# MatrixClock.net
KiCad netlist of a schematic drawn in EasyEDA Pro
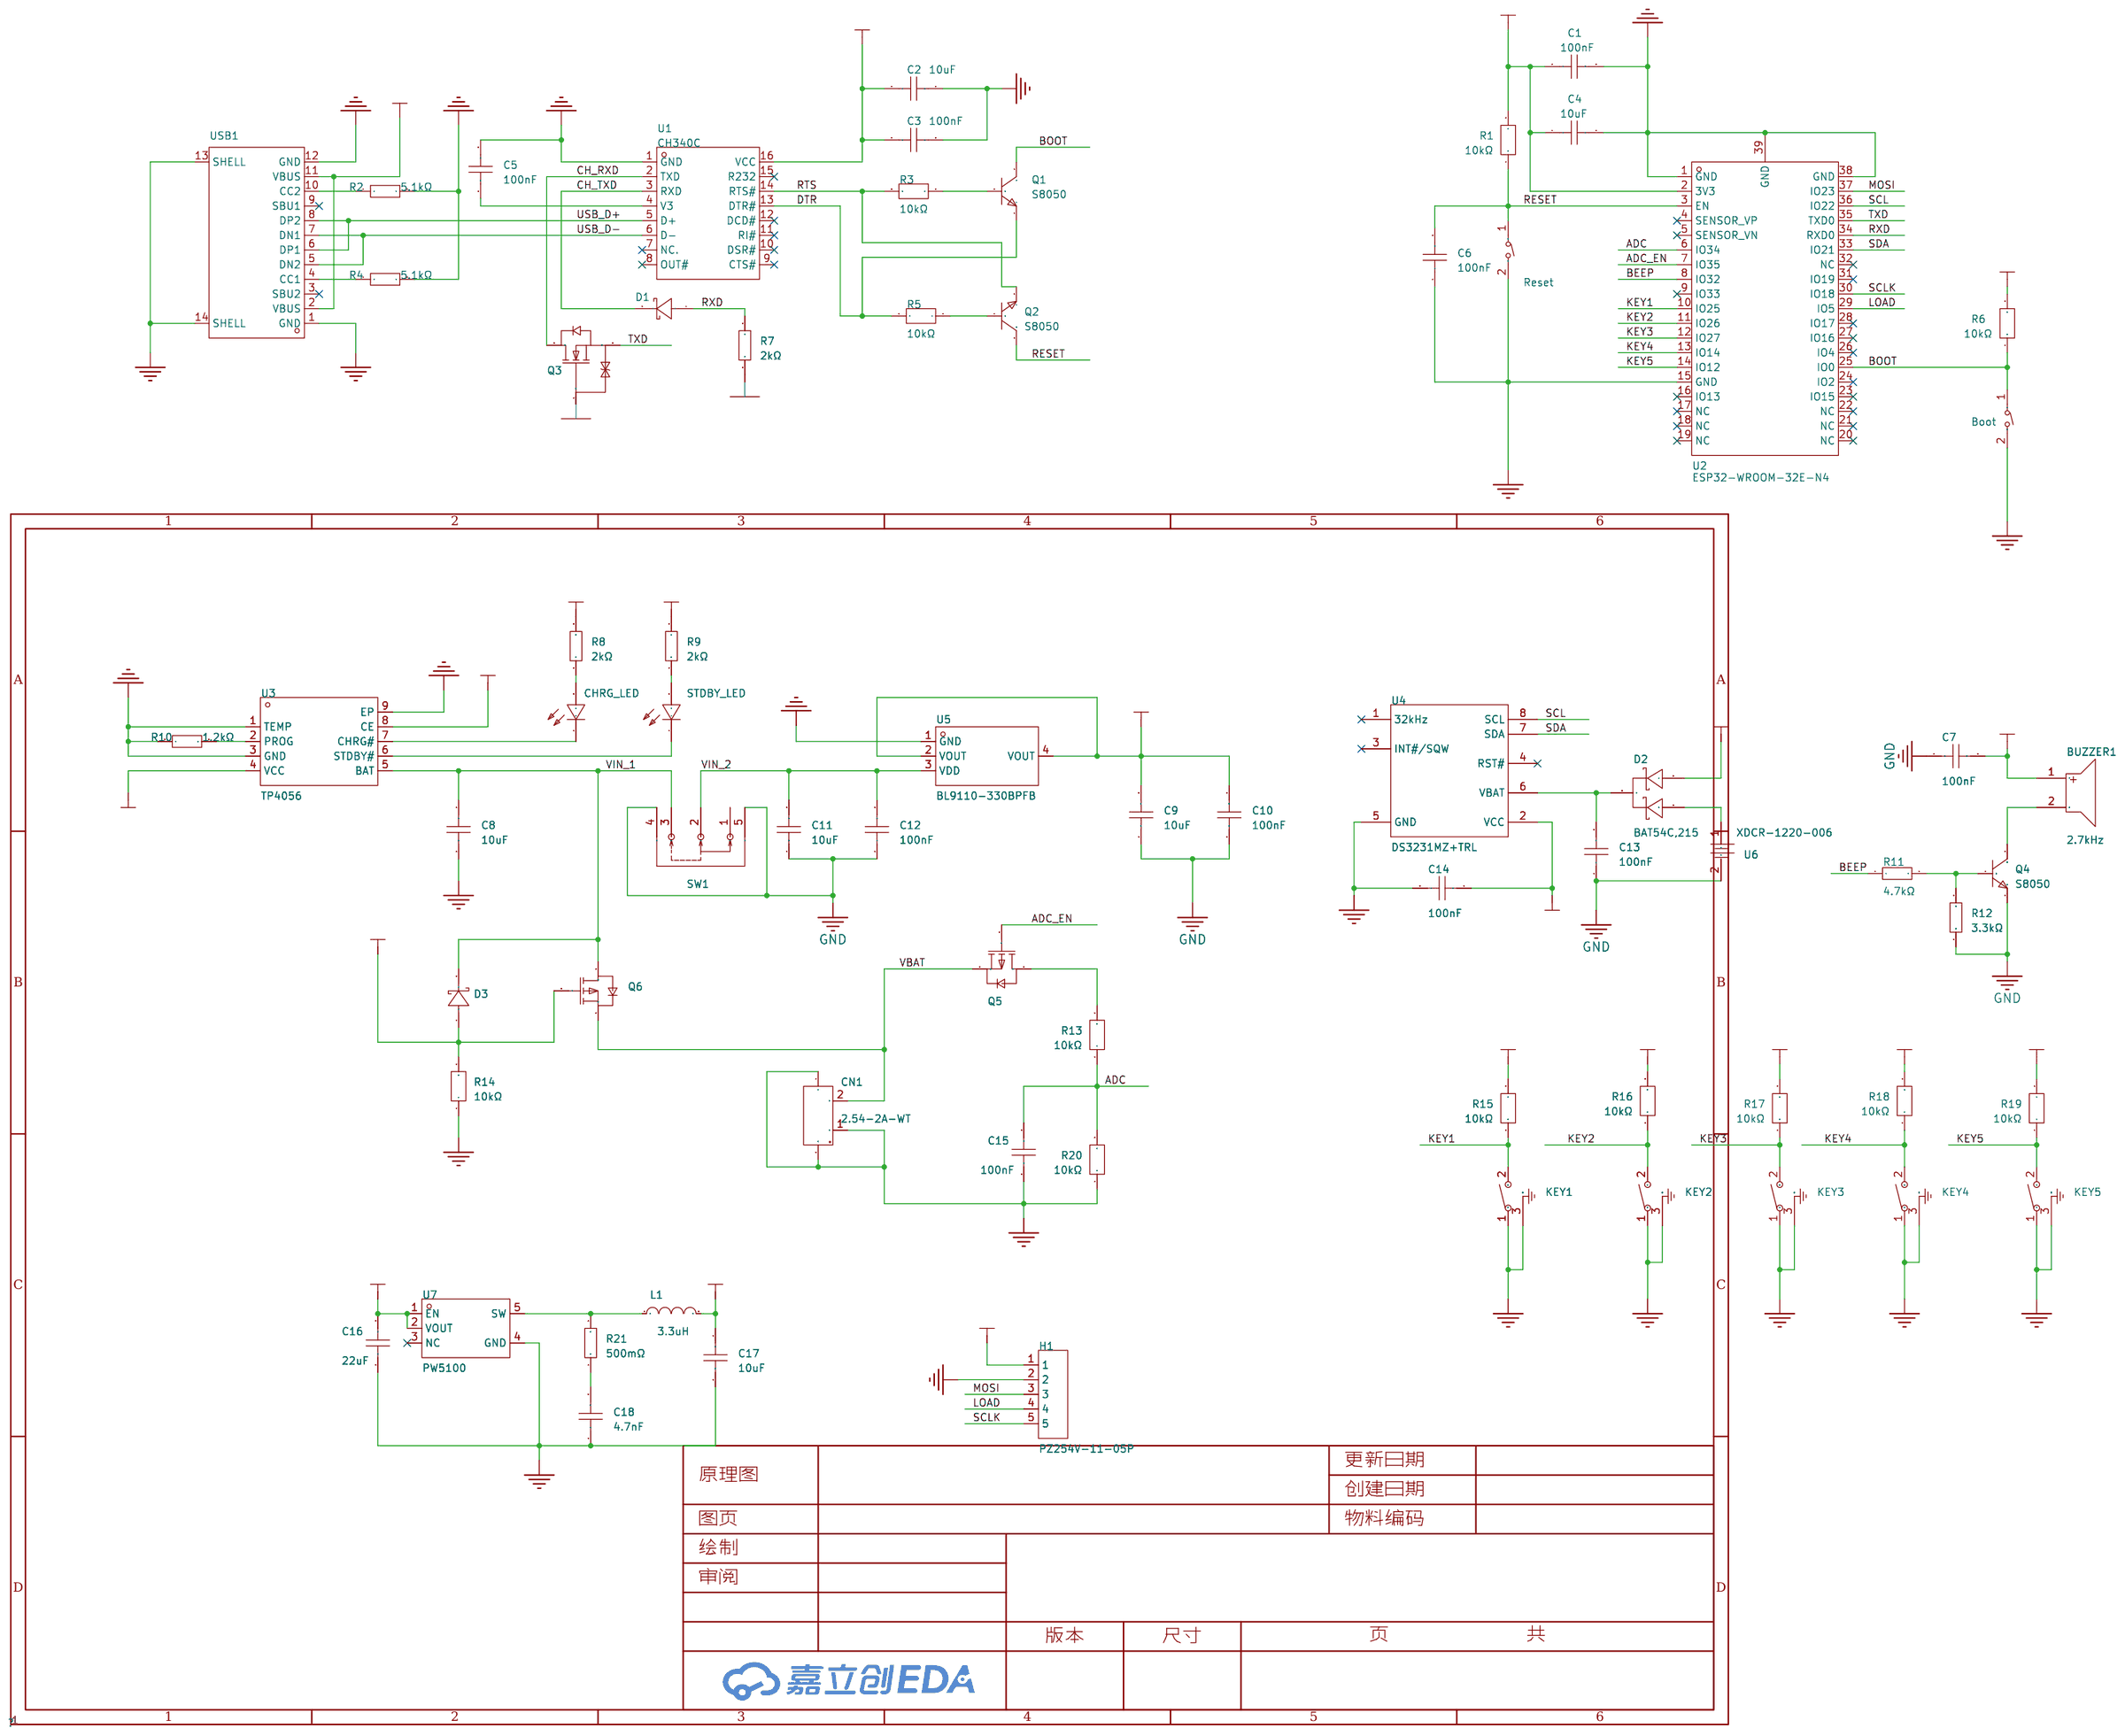
[diagram p0: schematic sheet]

(export (version "E")
  (design (tool "Eeschema 10.0.6"))
  (components
    (comp (ref "Boot")
      (value "ZX-QC34-2TPDZ")
      (fields (field (name "Manufacturer") "Megastar(兆星)"))
      (libsource (lib "easyedapro") (part "ZX-QC36-4.3TPWD"))
    )
    (comp (ref "BUZZER1")
      (value "2.7kHz")
      (footprint "easyedapro:BUZ-TH_BD9.0-P4.00-D0.6-FD")
      (description "驱动方式:无源(外部驱动);构造类型:电磁式;频率:2.7kHz;声压(SPL):85dB;")
      (fields (field (name "Manufacturer Part") "QMB-09B-03") (field (name "Manufacturer") "华能"))
      (libsource (lib "easyedapro") (part "QMB-09B-03"))
    )
    (comp (ref "C1")
      (value "100nF")
      (footprint "easyedapro:C0603")
      (description "容值:100nF;精度:±10%;额定电压:50V;材质(温度系数):X7R;")
      (fields
        (field (name "Manufacturer Part") "CC0603KRX7R9BB104")
        (field (name "Manufacturer") "YAGEO(国巨)")
      )
      (libsource (lib "easyedapro") (part "CC0603KRX7R9BB104"))
    )
    (comp (ref "C2")
      (value "10uF")
      (footprint "easyedapro:C0603")
      (description "容值:10uF;精度:±20%;额定电压:25V;材质(温度系数):X5R;")
      (fields
        (field (name "Manufacturer Part") "CL10A106MA8NRNC")
        (field (name "Manufacturer") "SAMSUNG(三星)")
      )
      (libsource (lib "easyedapro") (part "CL10A106MA8NRNC"))
    )
    (comp (ref "C3")
      (value "100nF")
      (footprint "easyedapro:C0603")
      (description "容值:100nF;精度:±10%;额定电压:50V;材质(温度系数):X7R;")
      (fields
        (field (name "Manufacturer Part") "CC0603KRX7R9BB104")
        (field (name "Manufacturer") "YAGEO(国巨)")
      )
      (libsource (lib "easyedapro") (part "CC0603KRX7R9BB104"))
    )
    (comp (ref "C4")
      (value "10uF")
      (footprint "easyedapro:C0603")
      (description "容值:10uF;精度:±20%;额定电压:25V;材质(温度系数):X5R;")
      (fields
        (field (name "Manufacturer Part") "CL10A106MA8NRNC")
        (field (name "Manufacturer") "SAMSUNG(三星)")
      )
      (libsource (lib "easyedapro") (part "CL10A106MA8NRNC"))
    )
    (comp (ref "C5")
      (value "100nF")
      (footprint "easyedapro:C0603")
      (description "容值:100nF;精度:±10%;额定电压:50V;材质(温度系数):X7R;")
      (fields
        (field (name "Manufacturer Part") "CC0603KRX7R9BB104")
        (field (name "Manufacturer") "YAGEO(国巨)")
      )
      (libsource (lib "easyedapro") (part "CC0603KRX7R9BB104"))
    )
    (comp (ref "C6")
      (value "100nF")
      (footprint "easyedapro:C0603")
      (description "容值:100nF;精度:±10%;额定电压:50V;材质(温度系数):X7R;")
      (fields
        (field (name "Manufacturer Part") "CC0603KRX7R9BB104")
        (field (name "Manufacturer") "YAGEO(国巨)")
      )
      (libsource (lib "easyedapro") (part "CC0603KRX7R9BB104"))
    )
    (comp (ref "C7")
      (value "100nF")
      (footprint "easyedapro:C0603")
      (description "容值:100nF;精度:±10%;额定电压:50V;材质(温度系数):X7R;")
      (fields
        (field (name "Manufacturer Part") "CC0603KRX7R9BB104")
        (field (name "Manufacturer") "YAGEO(国巨)")
      )
      (libsource (lib "easyedapro") (part "CC0603KRX7R9BB104"))
    )
    (comp (ref "C8")
      (value "10uF")
      (footprint "easyedapro:C0603")
      (description "容值:10uF;精度:±20%;额定电压:25V;材质(温度系数):X5R;")
      (fields
        (field (name "Manufacturer Part") "CL10A106MA8NRNC")
        (field (name "Manufacturer") "SAMSUNG(三星)")
      )
      (libsource (lib "easyedapro") (part "CL10A106MA8NRNC"))
    )
    (comp (ref "C9")
      (value "10uF")
      (footprint "easyedapro:C0603")
      (description "容值:10uF;精度:±20%;额定电压:25V;材质(温度系数):X5R;")
      (fields
        (field (name "Manufacturer Part") "CL10A106MA8NRNC")
        (field (name "Manufacturer") "SAMSUNG(三星)")
      )
      (libsource (lib "easyedapro") (part "CL10A106MA8NRNC"))
    )
    (comp (ref "C10")
      (value "100nF")
      (footprint "easyedapro:C0603")
      (description "容值:100nF;精度:±10%;额定电压:50V;材质(温度系数):X7R;")
      (fields
        (field (name "Manufacturer Part") "CC0603KRX7R9BB104")
        (field (name "Manufacturer") "YAGEO(国巨)")
      )
      (libsource (lib "easyedapro") (part "CC0603KRX7R9BB104"))
    )
    (comp (ref "C11")
      (value "10uF")
      (footprint "easyedapro:C0603")
      (description "容值:10uF;精度:±20%;额定电压:25V;材质(温度系数):X5R;")
      (fields
        (field (name "Manufacturer Part") "CL10A106MA8NRNC")
        (field (name "Manufacturer") "SAMSUNG(三星)")
      )
      (libsource (lib "easyedapro") (part "CL10A106MA8NRNC"))
    )
    (comp (ref "C12")
      (value "100nF")
      (footprint "easyedapro:C0603")
      (description "容值:100nF;精度:±10%;额定电压:50V;材质(温度系数):X7R;")
      (fields
        (field (name "Manufacturer Part") "CC0603KRX7R9BB104")
        (field (name "Manufacturer") "YAGEO(国巨)")
      )
      (libsource (lib "easyedapro") (part "CC0603KRX7R9BB104"))
    )
    (comp (ref "C13")
      (value "100nF")
      (footprint "easyedapro:C0603")
      (description "容值:100nF;精度:±10%;额定电压:50V;材质(温度系数):X7R;")
      (fields
        (field (name "Manufacturer Part") "CC0603KRX7R9BB104")
        (field (name "Manufacturer") "YAGEO(国巨)")
      )
      (libsource (lib "easyedapro") (part "CC0603KRX7R9BB104"))
    )
    (comp (ref "C14")
      (value "100nF")
      (footprint "easyedapro:C0603")
      (description "容值:100nF;精度:±10%;额定电压:50V;材质(温度系数):X7R;")
      (fields
        (field (name "Manufacturer Part") "CC0603KRX7R9BB104")
        (field (name "Manufacturer") "YAGEO(国巨)")
      )
      (libsource (lib "easyedapro") (part "CC0603KRX7R9BB104"))
    )
    (comp (ref "C15")
      (value "100nF")
      (footprint "easyedapro:C0603")
      (description "容值:100nF;精度:±10%;额定电压:50V;材质(温度系数):X7R;")
      (fields
        (field (name "Manufacturer Part") "CC0603KRX7R9BB104")
        (field (name "Manufacturer") "YAGEO(国巨)")
      )
      (libsource (lib "easyedapro") (part "CC0603KRX7R9BB104"))
    )
    (comp (ref "C16")
      (value "22uF")
      (fields
        (field (name "Manufacturer Part") "CGA0603X5R226M160JT")
        (field (name "Manufacturer") "HRE(芯声)")
      )
      (libsource (lib "easyedapro") (part "CapAcitance"))
    )
    (comp (ref "C17")
      (value "10uF")
      (footprint "easyedapro:C0603")
      (description "容值:10uF;精度:±20%;额定电压:25V;材质(温度系数):X5R;")
      (fields
        (field (name "Manufacturer Part") "CL10A106MA8NRNC")
        (field (name "Manufacturer") "SAMSUNG(三星)")
      )
      (libsource (lib "easyedapro") (part "CL10A106MA8NRNC"))
    )
    (comp (ref "C18")
      (value "4.7nF")
      (footprint "easyedapro:C0603")
      (description "容值:4.7nF;精度:±10%;额定电压:50V;材质(温度系数):X7R;")
      (fields
        (field (name "Manufacturer Part") "CGA0603X7R472K500JT")
        (field (name "Manufacturer") "HRE(芯声)")
      )
      (libsource (lib "easyedapro") (part "CGA0603X7R472K500JT"))
    )
    (comp (ref "CHRG_LED")
      (value "NCD0603R1")
      (footprint "easyedapro:LED0603-RD_RED")
      (fields (field (name "Manufacturer") "国星光电"))
      (libsource (lib "easyedapro") (part "FC-DA1608HRK-620D"))
    )
    (comp (ref "CN1")
      (value "2.54-2A-WT")
      (footprint "easyedapro:CONN-SMD_2.54-2A-WT")
      (description "插针结构:1x2P;间距:2.54mm;安装方式:卧贴;参考系列:XH;总PIN数:2P;排数:1;每排PIN数:2;行距:-;额定电流:500mA;工作温度范围:-25°C~+85°C;")
      (fields (field (name "Manufacturer") "CAX(创都)"))
      (libsource (lib "easyedapro") (part "2.54-2A-WT"))
    )
    (comp (ref "D1")
      (value "B5819WS")
      (footprint "easyedapro:SOD-323_L1.7-W1.3-LS2.5-FD")
      (description "二极管配置:独立式;正向压降(Vf):600mV@1.0A;直流反向耐压(Vr):40V;平均整流电流(Io):1A;")
      (fields (field (name "Manufacturer") "宏迦橙"))
      (libsource (lib "easyedapro") (part "B5819WS_C7420331"))
    )
    (comp (ref "D2")
      (value "BAT54C,215")
      (footprint "easyedapro:SOT-23-3_L2.9-W1.6-P1.90-LS2.8-BR")
      (description "二极管配置:1对共阴极;正向压降(Vf):800mV@100mA;直流反向耐压(Vr):30V;整流电流:200mA;")
      (fields (field (name "Manufacturer") "Nexperia(安世)"))
      (libsource (lib "easyedapro") (part "BAT54C,215"))
    )
    (comp (ref "D3")
      (value "B5819WS")
      (footprint "easyedapro:SOD-323_L1.7-W1.3-LS2.5-FD")
      (description "二极管配置:独立式;正向压降(Vf):600mV@1.0A;直流反向耐压(Vr):40V;平均整流电流(Io):1A;")
      (fields (field (name "Manufacturer") "宏迦橙"))
      (libsource (lib "easyedapro") (part "B5819WS_C7420331"))
    )
    (comp (ref "H1")
      (value "PZ254V-11-05P")
      (footprint "easyedapro:HDR-TH_5P-P2.54-V-M")
      (fields (field (name "Manufacturer") "XFCN(兴飞)"))
      (libsource (lib "easyedapro") (part "PZ254V-11-05P"))
    )
    (comp (ref "KEY1")
      (value "TS-1045-A13B3-D2")
      (footprint "easyedapro:SW-SMD_L7.5-W8.0-P4.50_TS-1045-A13B3-D2")
      (description "电路结构:单刀单掷;按钮形状:圆形按钮;作用力:250gf;安装方式:卧贴;开关高度:10mm;带支架:带支架;机械寿命:-;")
      (fields (field (name "Manufacturer") "Yuandi(元迪)"))
      (libsource (lib "easyedapro") (part "TS-1045-A13B3-D2"))
    )
    (comp (ref "KEY2")
      (value "TS-1045-A13B3-D2")
      (footprint "easyedapro:SW-SMD_L7.5-W8.0-P4.50_TS-1045-A13B3-D2")
      (description "电路结构:单刀单掷;按钮形状:圆形按钮;作用力:250gf;安装方式:卧贴;开关高度:10mm;带支架:带支架;机械寿命:-;")
      (fields (field (name "Manufacturer") "Yuandi(元迪)"))
      (libsource (lib "easyedapro") (part "TS-1045-A13B3-D2"))
    )
    (comp (ref "KEY3")
      (value "TS-1045-A13B3-D2")
      (footprint "easyedapro:SW-SMD_L7.5-W8.0-P4.50_TS-1045-A13B3-D2")
      (description "电路结构:单刀单掷;按钮形状:圆形按钮;作用力:250gf;安装方式:卧贴;开关高度:10mm;带支架:带支架;机械寿命:-;")
      (fields (field (name "Manufacturer") "Yuandi(元迪)"))
      (libsource (lib "easyedapro") (part "TS-1045-A13B3-D2"))
    )
    (comp (ref "KEY4")
      (value "TS-1045-A13B3-D2")
      (footprint "easyedapro:SW-SMD_L7.5-W8.0-P4.50_TS-1045-A13B3-D2")
      (description "电路结构:单刀单掷;按钮形状:圆形按钮;作用力:250gf;安装方式:卧贴;开关高度:10mm;带支架:带支架;机械寿命:-;")
      (fields (field (name "Manufacturer") "Yuandi(元迪)"))
      (libsource (lib "easyedapro") (part "TS-1045-A13B3-D2"))
    )
    (comp (ref "KEY5")
      (value "TS-1045-A13B3-D2")
      (footprint "easyedapro:SW-SMD_L7.5-W8.0-P4.50_TS-1045-A13B3-D2")
      (description "电路结构:单刀单掷;按钮形状:圆形按钮;作用力:250gf;安装方式:卧贴;开关高度:10mm;带支架:带支架;机械寿命:-;")
      (fields (field (name "Manufacturer") "Yuandi(元迪)"))
      (libsource (lib "easyedapro") (part "TS-1045-A13B3-D2"))
    )
    (comp (ref "L1")
      (value "3.3uH")
      (fields (field (name "Manufacturer Part") "FXL0420-3R3-M") (field (name "Manufacturer") "cjiang(长江微电)"))
      (libsource (lib "easyedapro") (part "CKST0402"))
    )
    (comp (ref "Q1")
      (value "S8050")
      (footprint "easyedapro:SOT-23-3_L2.9-W1.3-P1.90-LS2.3-BR")
      (description "晶体管类型:NPN;集电极电流(Ic):500mA;集射极击穿电压(Vceo):25V;功率(Pd):300mW;直流电流增益(hFE@Ic,Vce):120@50mA,1.0V;")
      (fields (field (name "Manufacturer") "宏迦橙"))
      (libsource (lib "easyedapro") (part "S8050_C20069125"))
    )
    (comp (ref "Q2")
      (value "S8050")
      (footprint "easyedapro:SOT-23-3_L2.9-W1.3-P1.90-LS2.3-BR")
      (description "晶体管类型:NPN;集电极电流(Ic):500mA;集射极击穿电压(Vceo):25V;功率(Pd):300mW;直流电流增益(hFE@Ic,Vce):120@50mA,1.0V;")
      (fields (field (name "Manufacturer") "宏迦橙"))
      (libsource (lib "easyedapro") (part "S8050_C20069125"))
    )
    (comp (ref "Q3")
      (value "2SK3018")
      (footprint "easyedapro:SOT-23-3_L2.9-W1.3-P1.90-LS2.4-BR")
      (fields (field (name "Manufacturer") "CJ(江苏长电/长晶)"))
      (libsource (lib "easyedapro") (part "2SK3018"))
    )
    (comp (ref "Q4")
      (value "S8050")
      (footprint "easyedapro:SOT-23-3_L2.9-W1.3-P1.90-LS2.3-BR")
      (description "晶体管类型:NPN;集电极电流(Ic):500mA;集射极击穿电压(Vceo):25V;功率(Pd):300mW;直流电流增益(hFE@Ic,Vce):120@50mA,1.0V;")
      (fields (field (name "Manufacturer") "宏迦橙"))
      (libsource (lib "easyedapro") (part "S8050_C20069125"))
    )
    (comp (ref "Q5")
      (value "SI2301CDS-T1-GE3-ES")
      (footprint "easyedapro:SOT-23-3_L2.9-W1.3-P1.90-LS2.4-BR")
      (fields (field (name "Manufacturer") "ElecSuper(静芯微)"))
      (libsource (lib "easyedapro") (part "SI2301CDS-T1-GE3-ES"))
    )
    (comp (ref "Q6")
      (value "SI2301CDS-T1-GE3-ES")
      (footprint "easyedapro:SOT-23-3_L2.9-W1.3-P1.90-LS2.4-BR")
      (fields (field (name "Manufacturer") "ElecSuper(静芯微)"))
      (libsource (lib "easyedapro") (part "SI2301CDS-T1-GE3-ES"))
    )
    (comp (ref "R1")
      (value "10kΩ")
      (fields (field (name "Manufacturer Part") "AC0603FR-0710KL") (field (name "Manufacturer") "YAGEO(国巨)"))
      (libsource (lib "easyedapro") (part "SG73P1JTTD1002F"))
    )
    (comp (ref "R2")
      (value "5.1kΩ")
      (fields (field (name "Manufacturer Part") "FRC0603F5101TS") (field (name "Manufacturer") "FOJAN(富捷)"))
      (libsource (lib "easyedapro") (part "RK73H1JTTD5101F"))
    )
    (comp (ref "R3")
      (value "10kΩ")
      (fields (field (name "Manufacturer Part") "AC0603FR-0710KL") (field (name "Manufacturer") "YAGEO(国巨)"))
      (libsource (lib "easyedapro") (part "SG73P1JTTD1002F"))
    )
    (comp (ref "R4")
      (value "5.1kΩ")
      (fields (field (name "Manufacturer Part") "FRC0603F5101TS") (field (name "Manufacturer") "FOJAN(富捷)"))
      (libsource (lib "easyedapro") (part "RK73H1JTTD5101F"))
    )
    (comp (ref "R5")
      (value "10kΩ")
      (fields (field (name "Manufacturer Part") "AC0603FR-0710KL") (field (name "Manufacturer") "YAGEO(国巨)"))
      (libsource (lib "easyedapro") (part "SG73P1JTTD1002F"))
    )
    (comp (ref "R6")
      (value "10kΩ")
      (fields (field (name "Manufacturer Part") "AC0603FR-0710KL") (field (name "Manufacturer") "YAGEO(国巨)"))
      (libsource (lib "easyedapro") (part "SG73P1JTTD1002F"))
    )
    (comp (ref "R7")
      (value "2kΩ")
      (footprint "easyedapro:R0603")
      (description "电阻类型:厚膜电阻;阻值:2kΩ;精度:±5%;功率:100mW;最大工作电压:75V;温度系数:±200ppm/°C;")
      (fields
        (field (name "Manufacturer Part") "0603WAF2001T5E")
        (field (name "Manufacturer") "UNI-ROYAL(厚声)")
      )
      (libsource (lib "easyedapro") (part "RK73B1JTTD202J"))
    )
    (comp (ref "R8")
      (value "2kΩ")
      (footprint "easyedapro:R0603")
      (description "电阻类型:厚膜电阻;阻值:2kΩ;精度:±5%;功率:100mW;最大工作电压:75V;温度系数:±200ppm/°C;")
      (fields
        (field (name "Manufacturer Part") "0603WAF2001T5E")
        (field (name "Manufacturer") "UNI-ROYAL(厚声)")
      )
      (libsource (lib "easyedapro") (part "RK73B1JTTD202J"))
    )
    (comp (ref "R9")
      (value "2kΩ")
      (footprint "easyedapro:R0603")
      (description "电阻类型:厚膜电阻;阻值:2kΩ;精度:±5%;功率:100mW;最大工作电压:75V;温度系数:±200ppm/°C;")
      (fields
        (field (name "Manufacturer Part") "0603WAF2001T5E")
        (field (name "Manufacturer") "UNI-ROYAL(厚声)")
      )
      (libsource (lib "easyedapro") (part "RK73B1JTTD202J"))
    )
    (comp (ref "R10")
      (value "1.2kΩ")
      (footprint "easyedapro:R0603")
      (description "电阻类型:厚膜电阻;阻值:1.2kΩ;精度:±1%;功率:100mW;最大工作电压:75V;温度系数:±100ppm/°C;")
      (fields
        (field (name "Manufacturer Part") "0603WAF1201T5E")
        (field (name "Manufacturer") "UNI-ROYAL(厚声)")
      )
      (libsource (lib "easyedapro") (part "0603WAF1201T5E"))
    )
    (comp (ref "R11")
      (value "4.7kΩ")
      (footprint "easyedapro:R0603")
      (description "电阻类型:厚膜电阻;阻值:4.7kΩ;精度:±1%;功率:100mW;最大工作电压:75V;温度系数:±100ppm/°C;")
      (fields (field (name "Manufacturer Part") "RC0603FR-074K7L") (field (name "Manufacturer") "YAGEO(国巨)"))
      (libsource (lib "easyedapro") (part "RC0603FR-074K7L"))
    )
    (comp (ref "R12")
      (value "3.3kΩ")
      (footprint "easyedapro:R0603")
      (description "电阻类型:厚膜电阻;阻值:3.3kΩ;精度:±1%;功率:100mW;最大工作电压:75V;温度系数:±100ppm/°C;")
      (fields (field (name "Manufacturer Part") "RC0603FR-073K3L") (field (name "Manufacturer") "YAGEO(国巨)"))
      (libsource (lib "easyedapro") (part "RC0603FR-073K3L"))
    )
    (comp (ref "R13")
      (value "10kΩ")
      (fields (field (name "Manufacturer Part") "AC0603FR-0710KL") (field (name "Manufacturer") "YAGEO(国巨)"))
      (libsource (lib "easyedapro") (part "SG73P1JTTD1002F"))
    )
    (comp (ref "R14")
      (value "10kΩ")
      (fields (field (name "Manufacturer Part") "AC0603FR-0710KL") (field (name "Manufacturer") "YAGEO(国巨)"))
      (libsource (lib "easyedapro") (part "SG73P1JTTD1002F"))
    )
    (comp (ref "R15")
      (value "10kΩ")
      (fields (field (name "Manufacturer Part") "AC0603FR-0710KL") (field (name "Manufacturer") "YAGEO(国巨)"))
      (libsource (lib "easyedapro") (part "SG73P1JTTD1002F"))
    )
    (comp (ref "R16")
      (value "10kΩ")
      (fields (field (name "Manufacturer Part") "AC0603FR-0710KL") (field (name "Manufacturer") "YAGEO(国巨)"))
      (libsource (lib "easyedapro") (part "SG73P1JTTD1002F"))
    )
    (comp (ref "R17")
      (value "10kΩ")
      (fields (field (name "Manufacturer Part") "AC0603FR-0710KL") (field (name "Manufacturer") "YAGEO(国巨)"))
      (libsource (lib "easyedapro") (part "SG73P1JTTD1002F"))
    )
    (comp (ref "R18")
      (value "10kΩ")
      (fields (field (name "Manufacturer Part") "AC0603FR-0710KL") (field (name "Manufacturer") "YAGEO(国巨)"))
      (libsource (lib "easyedapro") (part "SG73P1JTTD1002F"))
    )
    (comp (ref "R19")
      (value "10kΩ")
      (fields (field (name "Manufacturer Part") "AC0603FR-0710KL") (field (name "Manufacturer") "YAGEO(国巨)"))
      (libsource (lib "easyedapro") (part "SG73P1JTTD1002F"))
    )
    (comp (ref "R20")
      (value "10kΩ")
      (fields (field (name "Manufacturer Part") "AC0603FR-0710KL") (field (name "Manufacturer") "YAGEO(国巨)"))
      (libsource (lib "easyedapro") (part "SG73P1JTTD1002F"))
    )
    (comp (ref "R21")
      (value "500mΩ")
      (footprint "easyedapro:R0603")
      (description "电阻类型:厚膜电阻;阻值:500mΩ;精度:±1%;功率:100mW;最大工作电压:75V;温度系数:±800ppm/°C;")
      (fields
        (field (name "Manufacturer Part") "0603WAF500LT5E")
        (field (name "Manufacturer") "UNI-ROYAL(厚声)")
      )
      (libsource (lib "easyedapro") (part "0603WAF500LT5E"))
    )
    (comp (ref "Reset")
      (value "ZX-QC34-2TPDZ")
      (fields (field (name "Manufacturer") "Megastar(兆星)"))
      (libsource (lib "easyedapro") (part "ZX-QC36-4.3TPWD"))
    )
    (comp (ref "STDBY_LED")
      (value "NCD0603C1")
      (footprint "easyedapro:LED0603-RD")
      (fields (field (name "Manufacturer") "国星光电"))
      (libsource (lib "easyedapro") (part "FC-D1608HGK-572C"))
    )
    (comp (ref "SW1")
      (value "SK12D07VG4")
      (footprint "easyedapro:SW-TH_SK12D07VG4")
      (description "电路结构:单刀双掷;安装方式:-;额定电流(DC):500mA;额定电压(DC):50V;额定电流(AC):-;额定电压(AC):-;机械寿命:5千次;")
      (fields (field (name "Manufacturer") "SHOU HAN(首韩)"))
      (libsource (lib "easyedapro") (part "SK12D07VG4"))
    )
    (comp (ref "U1")
      (value "CH340C")
      (footprint "easyedapro:SOP-16_L10.0-W3.9-P1.27-LS6.0-BL")
      (description "应用功能:收发器;接口协议:USB 2.0;数据速率:2Mbps;")
      (fields (field (name "Manufacturer") "WCH(南京沁恒)"))
      (libsource (lib "easyedapro") (part "CH340C"))
    )
    (comp (ref "U2")
      (value "ESP32-WROOM-32E-N4")
      (footprint "easyedapro:WIFI-SMD_ESP32-WROOM-32E")
      (description "ESP32-WROOM-32E 集成 ESP32-D0WD-V3 芯片，具有高的稳定性和安全性能。")
      (fields (field (name "Manufacturer") "ESPRESSIF(乐鑫)"))
      (libsource (lib "easyedapro") (part "ESP32-WROOM-32E(4MB)"))
    )
    (comp (ref "U3")
      (value "TP4056")
      (footprint "easyedapro:ESOP-8_L4.9-W3.9-P1.27-LS6.0-BL-EP")
      (fields (field (name "Manufacturer") "UMW(友台半导体)"))
      (libsource (lib "easyedapro") (part "TP4056_C725790"))
    )
    (comp (ref "U4")
      (value "DS3231MZ+TRL")
      (footprint "easyedapro:SOIC-8_L4.9-W3.9-P1.27-LS6.0-BL")
      (description "接口:I2C;")
      (fields (field (name "Manufacturer") "ADI(亚德诺)/MAXIM(美信)"))
      (libsource (lib "easyedapro") (part "DS3231MZ+"))
    )
    (comp (ref "U5")
      (value "BL9110-330BPFB")
      (footprint "easyedapro:SOT-223_L6.5-W3.5-P2.30-LS7.0-BR")
      (description "输出类型:固定;输出极性:正;输出通道数:1;最大输入电压:6V;输出电压:3.3V;压差:390mV@(1A);输出电流:1A;电源纹波抑制比(PRSS):70dB@(1kHz);")
      (fields (field (name "Manufacturer") "BL(上海贝岭)"))
      (libsource (lib "easyedapro") (part "BL9110-330BPFB"))
    )
    (comp (ref "U6")
      (value "XDCR-1220-006")
      (footprint "easyedapro:BAT-SMD_CR1220-2ZX")
      (description "连接器类型:电池底座;适用电池规格:CR1220;触头材质:-;触点电镀:金;工作温度范围:-40°C~+85°C;")
      (fields (field (name "Manufacturer") "LX(连欣科技)"))
      (libsource (lib "easyedapro") (part "XDCR-1220-006"))
    )
    (comp (ref "U7")
      (value "PW5100")
      (footprint "easyedapro:SOT-23-5_L2.9-W1.6-P0.95-LS2.8-BL")
      (libsource (lib "easyedapro") (part "PW5100"))
    )
    (comp (ref "USB1")
      (value "TYPE-C 16PIN 2MD(073)")
      (footprint "easyedapro:USB-C-SMD_TYPE-C-6PIN-2MD-073")
      (description "连接器类型:Type-C;标准:-;公母:母;端口数量:1;触点数量:16P;安装方式:卧贴;额定电流 - 电源:5A;工作温度范围:-25°C~+85°C;")
      (fields (field (name "Manufacturer") "SHOU HAN(首韩)"))
      (libsource (lib "easyedapro") (part "TYPE-C 16PIN 2MD(073)"))
    )
  )
  (nets
    (net (code "1") (name "/ADC") (class "Default")
      (node (ref "C15") (pin "2") (pinfunction "2_2") (pintype "unspecified"))
      (node (ref "R13") (pin "1") (pinfunction "1_1") (pintype "input"))
      (node (ref "R20") (pin "2") (pinfunction "2_2") (pintype "input"))
      (node (ref "U2") (pin "6") (pinfunction "IO34_6") (pintype "unspecified"))
    )
    (net (code "2") (name "/ADC_EN") (class "Default")
      (node (ref "Q5") (pin "1") (pinfunction "G_1") (pintype "unspecified"))
      (node (ref "U2") (pin "7") (pinfunction "IO35_7") (pintype "unspecified"))
    )
    (net (code "3") (name "/BEEP") (class "Default")
      (node (ref "R11") (pin "1") (pinfunction "1_1") (pintype "input"))
      (node (ref "U2") (pin "8") (pinfunction "IO32_8") (pintype "unspecified"))
    )
    (net (code "4") (name "/BOOT") (class "Default")
      (node (ref "Boot") (pin "1") (pinfunction "1_1") (pintype "unspecified"))
      (node (ref "Q1") (pin "3") (pinfunction "C_3") (pintype "input"))
      (node (ref "R6") (pin "1") (pinfunction "1_1") (pintype "input"))
      (node (ref "U2") (pin "25") (pinfunction "IO0_25") (pintype "unspecified"))
    )
    (net (code "5") (name "/CH_RXD") (class "Default")
      (node (ref "Q3") (pin "3") (pinfunction "D_3") (pintype "unspecified"))
      (node (ref "U1") (pin "2") (pinfunction "TXD_2") (pintype "unspecified"))
    )
    (net (code "6") (name "/CH_TXD") (class "Default")
      (node (ref "D1") (pin "2") (pinfunction "K_2") (pintype "unspecified"))
      (node (ref "U1") (pin "3") (pinfunction "RXD_3") (pintype "unspecified"))
    )
    (net (code "7") (name "/DTR") (class "Default")
      (node (ref "Q1") (pin "2") (pinfunction "E_2") (pintype "input"))
      (node (ref "R5") (pin "2") (pinfunction "2_2") (pintype "input"))
      (node (ref "U1") (pin "13") (pinfunction "DTR#_13") (pintype "unspecified"))
    )
    (net (code "8") (name "/KEY1") (class "Default")
      (node (ref "KEY1") (pin "2") (pinfunction "2_2") (pintype "unspecified"))
      (node (ref "R15") (pin "1") (pinfunction "1_1") (pintype "input"))
      (node (ref "U2") (pin "10") (pinfunction "IO25_10") (pintype "unspecified"))
    )
    (net (code "9") (name "/KEY2") (class "Default")
      (node (ref "KEY2") (pin "2") (pinfunction "2_2") (pintype "unspecified"))
      (node (ref "R16") (pin "1") (pinfunction "1_1") (pintype "input"))
      (node (ref "U2") (pin "11") (pinfunction "IO26_11") (pintype "unspecified"))
    )
    (net (code "10") (name "/KEY3") (class "Default")
      (node (ref "KEY3") (pin "2") (pinfunction "2_2") (pintype "unspecified"))
      (node (ref "R17") (pin "1") (pinfunction "1_1") (pintype "input"))
      (node (ref "U2") (pin "12") (pinfunction "IO27_12") (pintype "unspecified"))
    )
    (net (code "11") (name "/KEY4") (class "Default")
      (node (ref "KEY4") (pin "2") (pinfunction "2_2") (pintype "unspecified"))
      (node (ref "R18") (pin "1") (pinfunction "1_1") (pintype "input"))
      (node (ref "U2") (pin "13") (pinfunction "IO14_13") (pintype "unspecified"))
    )
    (net (code "12") (name "/KEY5") (class "Default")
      (node (ref "KEY5") (pin "2") (pinfunction "2_2") (pintype "unspecified"))
      (node (ref "R19") (pin "1") (pinfunction "1_1") (pintype "input"))
      (node (ref "U2") (pin "14") (pinfunction "IO12_14") (pintype "unspecified"))
    )
    (net (code "13") (name "/LOAD") (class "Default")
      (node (ref "H1") (pin "4") (pinfunction "4_4") (pintype "unspecified"))
      (node (ref "U2") (pin "29") (pinfunction "IO5_29") (pintype "unspecified"))
    )
    (net (code "14") (name "/MOSI") (class "Default")
      (node (ref "H1") (pin "3") (pinfunction "3_3") (pintype "unspecified"))
      (node (ref "U2") (pin "37") (pinfunction "IO23_37") (pintype "unspecified"))
    )
    (net (code "15") (name "/RESET") (class "Default")
      (node (ref "C6") (pin "2") (pinfunction "2_2") (pintype "unspecified"))
      (node (ref "Q2") (pin "3") (pinfunction "C_3") (pintype "input"))
      (node (ref "R1") (pin "1") (pinfunction "1_1") (pintype "input"))
      (node (ref "Reset") (pin "1") (pinfunction "1_1") (pintype "unspecified"))
      (node (ref "U2") (pin "3") (pinfunction "EN_3") (pintype "unspecified"))
    )
    (net (code "16") (name "/RTS") (class "Default")
      (node (ref "Q2") (pin "2") (pinfunction "E_2") (pintype "input"))
      (node (ref "R3") (pin "2") (pinfunction "2_2") (pintype "input"))
      (node (ref "U1") (pin "14") (pinfunction "RTS#_14") (pintype "unspecified"))
    )
    (net (code "17") (name "/RXD") (class "Default")
      (node (ref "D1") (pin "1") (pinfunction "A_1") (pintype "unspecified"))
      (node (ref "R7") (pin "1") (pinfunction "1_1") (pintype "unspecified"))
      (node (ref "U2") (pin "34") (pinfunction "RXD0_34") (pintype "unspecified"))
    )
    (net (code "18") (name "/SCL") (class "Default")
      (node (ref "U2") (pin "36") (pinfunction "IO22_36") (pintype "unspecified"))
      (node (ref "U4") (pin "8") (pinfunction "SCL_8") (pintype "unspecified"))
    )
    (net (code "19") (name "/SCLK") (class "Default")
      (node (ref "H1") (pin "5") (pinfunction "5_5") (pintype "unspecified"))
      (node (ref "U2") (pin "30") (pinfunction "IO18_30") (pintype "unspecified"))
    )
    (net (code "20") (name "/SDA") (class "Default")
      (node (ref "U2") (pin "33") (pinfunction "IO21_33") (pintype "unspecified"))
      (node (ref "U4") (pin "7") (pinfunction "SDA_7") (pintype "bidirectional"))
    )
    (net (code "21") (name "/TXD") (class "Default")
      (node (ref "Q3") (pin "2") (pinfunction "S_2") (pintype "unspecified"))
      (node (ref "U2") (pin "35") (pinfunction "TXD0_35") (pintype "unspecified"))
    )
    (net (code "22") (name "/USB_D+") (class "Default")
      (node (ref "U1") (pin "5") (pinfunction "D+_5") (pintype "unspecified"))
      (node (ref "USB1") (pin "6") (pinfunction "DP1_6") (pintype "unspecified"))
      (node (ref "USB1") (pin "8") (pinfunction "DP2_8") (pintype "unspecified"))
    )
    (net (code "23") (name "/USB_D-") (class "Default")
      (node (ref "U1") (pin "6") (pinfunction "D-_6") (pintype "unspecified"))
      (node (ref "USB1") (pin "5") (pinfunction "DN2_5") (pintype "unspecified"))
      (node (ref "USB1") (pin "7") (pinfunction "DN1_7") (pintype "unspecified"))
    )
    (net (code "24") (name "/VBAT") (class "Default")
      (node (ref "CN1") (pin "2") (pinfunction "2_2") (pintype "input"))
      (node (ref "Q5") (pin "2") (pinfunction "S_2") (pintype "unspecified"))
      (node (ref "Q6") (pin "2") (pinfunction "S_2") (pintype "unspecified"))
    )
    (net (code "25") (name "/VIN_1") (class "Default")
      (node (ref "C8") (pin "1") (pinfunction "1_1") (pintype "unspecified"))
      (node (ref "D3") (pin "2") (pinfunction "K_2") (pintype "unspecified"))
      (node (ref "Q6") (pin "3") (pinfunction "D_3") (pintype "unspecified"))
      (node (ref "SW1") (pin "3") (pinfunction "3_3") (pintype "unspecified"))
      (node (ref "U3") (pin "5") (pinfunction "BAT_5") (pintype "unspecified"))
    )
    (net (code "26") (name "3V3") (class "Default")
      (node (ref "BUZZER1") (pin "1") (pinfunction "1_1") (pintype "unspecified"))
      (node (ref "C1") (pin "1") (pinfunction "1_1") (pintype "unspecified"))
      (node (ref "C10") (pin "2") (pinfunction "2_2") (pintype "unspecified"))
      (node (ref "C14") (pin "1") (pinfunction "1_1") (pintype "unspecified"))
      (node (ref "C4") (pin "1") (pinfunction "1_1") (pintype "unspecified"))
      (node (ref "C7") (pin "2") (pinfunction "2_2") (pintype "unspecified"))
      (node (ref "C9") (pin "2") (pinfunction "2_2") (pintype "unspecified"))
      (node (ref "D2") (pin "2") (pinfunction "A_2") (pintype "unspecified"))
      (node (ref "Q3") (pin "1") (pinfunction "G_1") (pintype "unspecified"))
      (node (ref "R1") (pin "2") (pinfunction "2_2") (pintype "input"))
      (node (ref "R15") (pin "2") (pinfunction "2_2") (pintype "input"))
      (node (ref "R16") (pin "2") (pinfunction "2_2") (pintype "input"))
      (node (ref "R17") (pin "2") (pinfunction "2_2") (pintype "input"))
      (node (ref "R18") (pin "2") (pinfunction "2_2") (pintype "input"))
      (node (ref "R19") (pin "2") (pinfunction "2_2") (pintype "input"))
      (node (ref "R6") (pin "2") (pinfunction "2_2") (pintype "input"))
      (node (ref "R7") (pin "2") (pinfunction "2_2") (pintype "unspecified"))
      (node (ref "U2") (pin "2") (pinfunction "3V3_2") (pintype "unspecified"))
      (node (ref "U4") (pin "2") (pinfunction "VCC_2") (pintype "unspecified"))
      (node (ref "U5") (pin "2") (pinfunction "VOUT_2") (pintype "input"))
      (node (ref "U5") (pin "4") (pinfunction "VOUT_4") (pintype "input"))
    )
    (net (code "27") (name "5V") (class "Default")
      (node (ref "C16") (pin "2") (pinfunction "2_2") (pintype "input"))
      (node (ref "H1") (pin "1") (pinfunction "1_1") (pintype "unspecified"))
      (node (ref "U7") (pin "1") (pinfunction "EN_1") (pintype "input"))
      (node (ref "U7") (pin "2") (pinfunction "VOUT_2") (pintype "input"))
    )
    (net (code "28") (name "GND") (class "Default")
      (node (ref "Boot") (pin "2") (pinfunction "2_2") (pintype "unspecified"))
      (node (ref "C1") (pin "2") (pinfunction "2_2") (pintype "unspecified"))
      (node (ref "C10") (pin "1") (pinfunction "1_1") (pintype "unspecified"))
      (node (ref "C11") (pin "1") (pinfunction "1_1") (pintype "unspecified"))
      (node (ref "C12") (pin "1") (pinfunction "1_1") (pintype "unspecified"))
      (node (ref "C13") (pin "1") (pinfunction "1_1") (pintype "unspecified"))
      (node (ref "C14") (pin "2") (pinfunction "2_2") (pintype "unspecified"))
      (node (ref "C15") (pin "1") (pinfunction "1_1") (pintype "unspecified"))
      (node (ref "C16") (pin "1") (pinfunction "1_1") (pintype "input"))
      (node (ref "C17") (pin "2") (pinfunction "2_2") (pintype "unspecified"))
      (node (ref "C18") (pin "1") (pinfunction "1_1") (pintype "unspecified"))
      (node (ref "C2") (pin "2") (pinfunction "2_2") (pintype "unspecified"))
      (node (ref "C3") (pin "2") (pinfunction "2_2") (pintype "unspecified"))
      (node (ref "C4") (pin "2") (pinfunction "2_2") (pintype "unspecified"))
      (node (ref "C5") (pin "2") (pinfunction "2_2") (pintype "unspecified"))
      (node (ref "C6") (pin "1") (pinfunction "1_1") (pintype "unspecified"))
      (node (ref "C7") (pin "1") (pinfunction "1_1") (pintype "unspecified"))
      (node (ref "C8") (pin "2") (pinfunction "2_2") (pintype "unspecified"))
      (node (ref "C9") (pin "1") (pinfunction "1_1") (pintype "unspecified"))
      (node (ref "CN1") (pin "1") (pinfunction "1_1") (pintype "input"))
      (node (ref "CN1") (pin "3") (pinfunction "3_3") (pintype "unspecified"))
      (node (ref "CN1") (pin "4") (pinfunction "4_4") (pintype "unspecified"))
      (node (ref "H1") (pin "2") (pinfunction "2_2") (pintype "unspecified"))
      (node (ref "KEY1") (pin "1") (pinfunction "1_1") (pintype "unspecified"))
      (node (ref "KEY1") (pin "3") (pinfunction "GND_3") (pintype "unspecified"))
      (node (ref "KEY2") (pin "1") (pinfunction "1_1") (pintype "unspecified"))
      (node (ref "KEY2") (pin "3") (pinfunction "GND_3") (pintype "unspecified"))
      (node (ref "KEY3") (pin "1") (pinfunction "1_1") (pintype "unspecified"))
      (node (ref "KEY3") (pin "3") (pinfunction "GND_3") (pintype "unspecified"))
      (node (ref "KEY4") (pin "1") (pinfunction "1_1") (pintype "unspecified"))
      (node (ref "KEY4") (pin "3") (pinfunction "GND_3") (pintype "unspecified"))
      (node (ref "KEY5") (pin "1") (pinfunction "1_1") (pintype "unspecified"))
      (node (ref "KEY5") (pin "3") (pinfunction "GND_3") (pintype "unspecified"))
      (node (ref "Q4") (pin "2") (pinfunction "E_2") (pintype "input"))
      (node (ref "R10") (pin "1") (pinfunction "1_1") (pintype "input"))
      (node (ref "R12") (pin "1") (pinfunction "1_1") (pintype "input"))
      (node (ref "R14") (pin "1") (pinfunction "1_1") (pintype "input"))
      (node (ref "R2") (pin "2") (pinfunction "2_2") (pintype "input"))
      (node (ref "R20") (pin "1") (pinfunction "1_1") (pintype "input"))
      (node (ref "R4") (pin "2") (pinfunction "2_2") (pintype "input"))
      (node (ref "Reset") (pin "2") (pinfunction "2_2") (pintype "unspecified"))
      (node (ref "SW1") (pin "4") (pinfunction "4_4") (pintype "unspecified"))
      (node (ref "SW1") (pin "5") (pinfunction "5_5") (pintype "unspecified"))
      (node (ref "U1") (pin "1") (pinfunction "GND_1") (pintype "unspecified"))
      (node (ref "U2") (pin "1") (pinfunction "GND_1") (pintype "unspecified"))
      (node (ref "U2") (pin "15") (pinfunction "GND_15") (pintype "unspecified"))
      (node (ref "U2") (pin "38") (pinfunction "GND_38") (pintype "unspecified"))
      (node (ref "U2") (pin "39") (pinfunction "GND_39") (pintype "unspecified"))
      (node (ref "U3") (pin "1") (pinfunction "TEMP_1") (pintype "unspecified"))
      (node (ref "U3") (pin "3") (pinfunction "GND_3") (pintype "unspecified"))
      (node (ref "U3") (pin "9") (pinfunction "EP_9") (pintype "unspecified"))
      (node (ref "U4") (pin "5") (pinfunction "GND_5") (pintype "unspecified"))
      (node (ref "U5") (pin "1") (pinfunction "GND_1") (pintype "input"))
      (node (ref "U6") (pin "2") (pinfunction "2_2") (pintype "input"))
      (node (ref "U7") (pin "4") (pinfunction "GND_4") (pintype "input"))
      (node (ref "USB1") (pin "1") (pinfunction "GND_1") (pintype "unspecified"))
      (node (ref "USB1") (pin "12") (pinfunction "GND_12") (pintype "unspecified"))
      (node (ref "USB1") (pin "13") (pinfunction "SHELL_13") (pintype "unspecified"))
      (node (ref "USB1") (pin "14") (pinfunction "SHELL_14") (pintype "unspecified"))
    )
    (net (code "29") (name "Net-(C18-Pad2)") (class "Default")
      (node (ref "C18") (pin "2") (pinfunction "2_2") (pintype "unspecified"))
      (node (ref "R21") (pin "1") (pinfunction "1_1") (pintype "input"))
    )
    (net (code "30") (name "Net-(CHRG_LED-A)") (class "Default")
      (node (ref "CHRG_LED") (pin "2") (pinfunction "A_2") (pintype "input"))
      (node (ref "R8") (pin "1") (pinfunction "1_1") (pintype "unspecified"))
    )
    (net (code "31") (name "Net-(CHRG_LED-K)") (class "Default")
      (node (ref "CHRG_LED") (pin "1") (pinfunction "K_1") (pintype "input"))
      (node (ref "U3") (pin "7") (pinfunction "CHRG#_7") (pintype "unspecified"))
    )
    (net (code "32") (name "Net-(D2-A-Pad1)") (class "Default")
      (node (ref "D2") (pin "1") (pinfunction "A_1") (pintype "unspecified"))
      (node (ref "U6") (pin "1") (pinfunction "1_1") (pintype "input"))
    )
    (net (code "33") (name "Net-(D2-K)") (class "Default")
      (node (ref "C13") (pin "2") (pinfunction "2_2") (pintype "unspecified"))
      (node (ref "D2") (pin "3") (pinfunction "K_3") (pintype "unspecified"))
      (node (ref "U4") (pin "6") (pinfunction "VBAT_6") (pintype "unspecified"))
    )
    (net (code "34") (name "Net-(Q1-B)") (class "Default")
      (node (ref "Q1") (pin "1") (pinfunction "B_1") (pintype "input"))
      (node (ref "R3") (pin "1") (pinfunction "1_1") (pintype "input"))
    )
    (net (code "35") (name "Net-(Q2-B)") (class "Default")
      (node (ref "Q2") (pin "1") (pinfunction "B_1") (pintype "input"))
      (node (ref "R5") (pin "1") (pinfunction "1_1") (pintype "input"))
    )
    (net (code "36") (name "Net-(Q4-B)") (class "Default")
      (node (ref "Q4") (pin "1") (pinfunction "B_1") (pintype "input"))
      (node (ref "R11") (pin "2") (pinfunction "2_2") (pintype "input"))
      (node (ref "R12") (pin "2") (pinfunction "2_2") (pintype "input"))
    )
    (net (code "37") (name "Net-(Q4-C)") (class "Default")
      (node (ref "BUZZER1") (pin "2") (pinfunction "2_2") (pintype "unspecified"))
      (node (ref "Q4") (pin "3") (pinfunction "C_3") (pintype "input"))
    )
    (net (code "38") (name "Net-(Q5-D)") (class "Default")
      (node (ref "Q5") (pin "3") (pinfunction "D_3") (pintype "unspecified"))
      (node (ref "R13") (pin "2") (pinfunction "2_2") (pintype "input"))
    )
    (net (code "39") (name "Net-(STDBY_LED-+)") (class "Default")
      (node (ref "R9") (pin "1") (pinfunction "1_1") (pintype "unspecified"))
      (node (ref "STDBY_LED") (pin "2") (pinfunction "+_2") (pintype "input"))
    )
    (net (code "40") (name "Net-(STDBY_LED--)") (class "Default")
      (node (ref "STDBY_LED") (pin "1") (pinfunction "-_1") (pintype "input"))
      (node (ref "U3") (pin "6") (pinfunction "STDBY#_6") (pintype "unspecified"))
    )
    (net (code "41") (name "Net-(U1-V3)") (class "Default")
      (node (ref "C5") (pin "1") (pinfunction "1_1") (pintype "unspecified"))
      (node (ref "U1") (pin "4") (pinfunction "V3_4") (pintype "unspecified"))
    )
    (net (code "42") (name "Net-(U3-PROG)") (class "Default")
      (node (ref "R10") (pin "2") (pinfunction "2_2") (pintype "input"))
      (node (ref "U3") (pin "2") (pinfunction "PROG_2") (pintype "unspecified"))
    )
    (net (code "43") (name "Net-(U7-SW)") (class "Default")
      (node (ref "L1") (pin "1") (pinfunction "1_1") (pintype "input"))
      (node (ref "R21") (pin "2") (pinfunction "2_2") (pintype "input"))
      (node (ref "U7") (pin "5") (pinfunction "SW_5") (pintype "input"))
    )
    (net (code "44") (name "Net-(USB1-CC1)") (class "Default")
      (node (ref "R4") (pin "1") (pinfunction "1_1") (pintype "input"))
      (node (ref "USB1") (pin "4") (pinfunction "CC1_4") (pintype "unspecified"))
    )
    (net (code "45") (name "Net-(USB1-CC2)") (class "Default")
      (node (ref "R2") (pin "1") (pinfunction "1_1") (pintype "input"))
      (node (ref "USB1") (pin "10") (pinfunction "CC2_10") (pintype "unspecified"))
    )
    (net (code "46") (name "VBUS") (class "Default")
      (node (ref "C2") (pin "1") (pinfunction "1_1") (pintype "unspecified"))
      (node (ref "C3") (pin "1") (pinfunction "1_1") (pintype "unspecified"))
      (node (ref "D3") (pin "1") (pinfunction "A_1") (pintype "unspecified"))
      (node (ref "Q6") (pin "1") (pinfunction "G_1") (pintype "unspecified"))
      (node (ref "R14") (pin "2") (pinfunction "2_2") (pintype "input"))
      (node (ref "R8") (pin "2") (pinfunction "2_2") (pintype "unspecified"))
      (node (ref "R9") (pin "2") (pinfunction "2_2") (pintype "unspecified"))
      (node (ref "U1") (pin "16") (pinfunction "VCC_16") (pintype "unspecified"))
      (node (ref "U3") (pin "4") (pinfunction "VCC_4") (pintype "unspecified"))
      (node (ref "U3") (pin "8") (pinfunction "CE_8") (pintype "unspecified"))
      (node (ref "USB1") (pin "11") (pinfunction "VBUS_11") (pintype "unspecified"))
      (node (ref "USB1") (pin "2") (pinfunction "VBUS_2") (pintype "unspecified"))
    )
    (net (code "47") (name "VIN_2") (class "Default")
      (node (ref "C11") (pin "2") (pinfunction "2_2") (pintype "unspecified"))
      (node (ref "C12") (pin "2") (pinfunction "2_2") (pintype "unspecified"))
      (node (ref "C17") (pin "1") (pinfunction "1_1") (pintype "unspecified"))
      (node (ref "L1") (pin "2") (pinfunction "2_2") (pintype "input"))
      (node (ref "SW1") (pin "2") (pinfunction "2_2") (pintype "unspecified"))
      (node (ref "U5") (pin "3") (pinfunction "VDD_3") (pintype "input"))
    )
    (net (code "48") (name "unconnected-(SW1-Pad1)") (class "Default")
      (node (ref "SW1") (pin "1") (pinfunction "1_1") (pintype "unspecified"))
    )
    (net (code "49") (name "unconnected-(U1-CTS#-Pad9)") (class "Default")
      (node (ref "U1") (pin "9") (pinfunction "CTS#_9") (pintype "unspecified+no_connect"))
    )
    (net (code "50") (name "unconnected-(U1-DCD#-Pad12)") (class "Default")
      (node (ref "U1") (pin "12") (pinfunction "DCD#_12") (pintype "unspecified+no_connect"))
    )
    (net (code "51") (name "unconnected-(U1-DSR#-Pad10)") (class "Default")
      (node (ref "U1") (pin "10") (pinfunction "DSR#_10") (pintype "unspecified+no_connect"))
    )
    (net (code "52") (name "unconnected-(U1-NC.-Pad7)") (class "Default")
      (node (ref "U1") (pin "7") (pinfunction "NC._7") (pintype "unspecified+no_connect"))
    )
    (net (code "53") (name "unconnected-(U1-OUT#-Pad8)") (class "Default")
      (node (ref "U1") (pin "8") (pinfunction "OUT#_8") (pintype "unspecified+no_connect"))
    )
    (net (code "54") (name "unconnected-(U1-R232-Pad15)") (class "Default")
      (node (ref "U1") (pin "15") (pinfunction "R232_15") (pintype "unspecified+no_connect"))
    )
    (net (code "55") (name "unconnected-(U1-RI#-Pad11)") (class "Default")
      (node (ref "U1") (pin "11") (pinfunction "RI#_11") (pintype "unspecified+no_connect"))
    )
    (net (code "56") (name "unconnected-(U2-IO2-Pad24)") (class "Default")
      (node (ref "U2") (pin "24") (pinfunction "IO2_24") (pintype "unspecified+no_connect"))
    )
    (net (code "57") (name "unconnected-(U2-IO4-Pad26)") (class "Default")
      (node (ref "U2") (pin "26") (pinfunction "IO4_26") (pintype "unspecified+no_connect"))
    )
    (net (code "58") (name "unconnected-(U2-IO13-Pad16)") (class "Default")
      (node (ref "U2") (pin "16") (pinfunction "IO13_16") (pintype "unspecified+no_connect"))
    )
    (net (code "59") (name "unconnected-(U2-IO15-Pad23)") (class "Default")
      (node (ref "U2") (pin "23") (pinfunction "IO15_23") (pintype "unspecified+no_connect"))
    )
    (net (code "60") (name "unconnected-(U2-IO16-Pad27)") (class "Default")
      (node (ref "U2") (pin "27") (pinfunction "IO16_27") (pintype "unspecified+no_connect"))
    )
    (net (code "61") (name "unconnected-(U2-IO17-Pad28)") (class "Default")
      (node (ref "U2") (pin "28") (pinfunction "IO17_28") (pintype "unspecified+no_connect"))
    )
    (net (code "62") (name "unconnected-(U2-IO19-Pad31)") (class "Default")
      (node (ref "U2") (pin "31") (pinfunction "IO19_31") (pintype "unspecified+no_connect"))
    )
    (net (code "63") (name "unconnected-(U2-IO33-Pad9)") (class "Default")
      (node (ref "U2") (pin "9") (pinfunction "IO33_9") (pintype "unspecified+no_connect"))
    )
    (net (code "64") (name "unconnected-(U2-NC-Pad17)") (class "Default")
      (node (ref "U2") (pin "17") (pinfunction "NC_17") (pintype "unspecified+no_connect"))
    )
    (net (code "65") (name "unconnected-(U2-NC-Pad18)") (class "Default")
      (node (ref "U2") (pin "18") (pinfunction "NC_18") (pintype "unspecified+no_connect"))
    )
    (net (code "66") (name "unconnected-(U2-NC-Pad19)") (class "Default")
      (node (ref "U2") (pin "19") (pinfunction "NC_19") (pintype "unspecified+no_connect"))
    )
    (net (code "67") (name "unconnected-(U2-NC-Pad20)") (class "Default")
      (node (ref "U2") (pin "20") (pinfunction "NC_20") (pintype "unspecified+no_connect"))
    )
    (net (code "68") (name "unconnected-(U2-NC-Pad21)") (class "Default")
      (node (ref "U2") (pin "21") (pinfunction "NC_21") (pintype "unspecified+no_connect"))
    )
    (net (code "69") (name "unconnected-(U2-NC-Pad22)") (class "Default")
      (node (ref "U2") (pin "22") (pinfunction "NC_22") (pintype "unspecified+no_connect"))
    )
    (net (code "70") (name "unconnected-(U2-NC-Pad32)") (class "Default")
      (node (ref "U2") (pin "32") (pinfunction "NC_32") (pintype "unspecified+no_connect"))
    )
    (net (code "71") (name "unconnected-(U2-SENSOR_VN-Pad5)") (class "Default")
      (node (ref "U2") (pin "5") (pinfunction "SENSOR_VN_5") (pintype "unspecified+no_connect"))
    )
    (net (code "72") (name "unconnected-(U2-SENSOR_VP-Pad4)") (class "Default")
      (node (ref "U2") (pin "4") (pinfunction "SENSOR_VP_4") (pintype "unspecified+no_connect"))
    )
    (net (code "73") (name "unconnected-(U4-32kHz-Pad1)") (class "Default")
      (node (ref "U4") (pin "1") (pinfunction "32kHz_1") (pintype "unspecified+no_connect"))
    )
    (net (code "74") (name "unconnected-(U4-INT#{slash}SQW-Pad3)") (class "Default")
      (node (ref "U4") (pin "3") (pinfunction "INT#/SQW_3") (pintype "bidirectional+no_connect"))
    )
    (net (code "75") (name "unconnected-(U4-RST#-Pad4)") (class "Default")
      (node (ref "U4") (pin "4") (pinfunction "RST#_4") (pintype "bidirectional+no_connect"))
    )
    (net (code "76") (name "unconnected-(U7-NC-Pad3)") (class "Default")
      (node (ref "U7") (pin "3") (pinfunction "NC_3") (pintype "input+no_connect"))
    )
    (net (code "77") (name "unconnected-(USB1-SBU1-Pad9)") (class "Default")
      (node (ref "USB1") (pin "9") (pinfunction "SBU1_9") (pintype "unspecified+no_connect"))
    )
    (net (code "78") (name "unconnected-(USB1-SBU2-Pad3)") (class "Default")
      (node (ref "USB1") (pin "3") (pinfunction "SBU2_3") (pintype "unspecified+no_connect"))
    )
  )
)
